# Sensor_Schem.net
KiCad netlist of a schematic drawn in Altium Designer
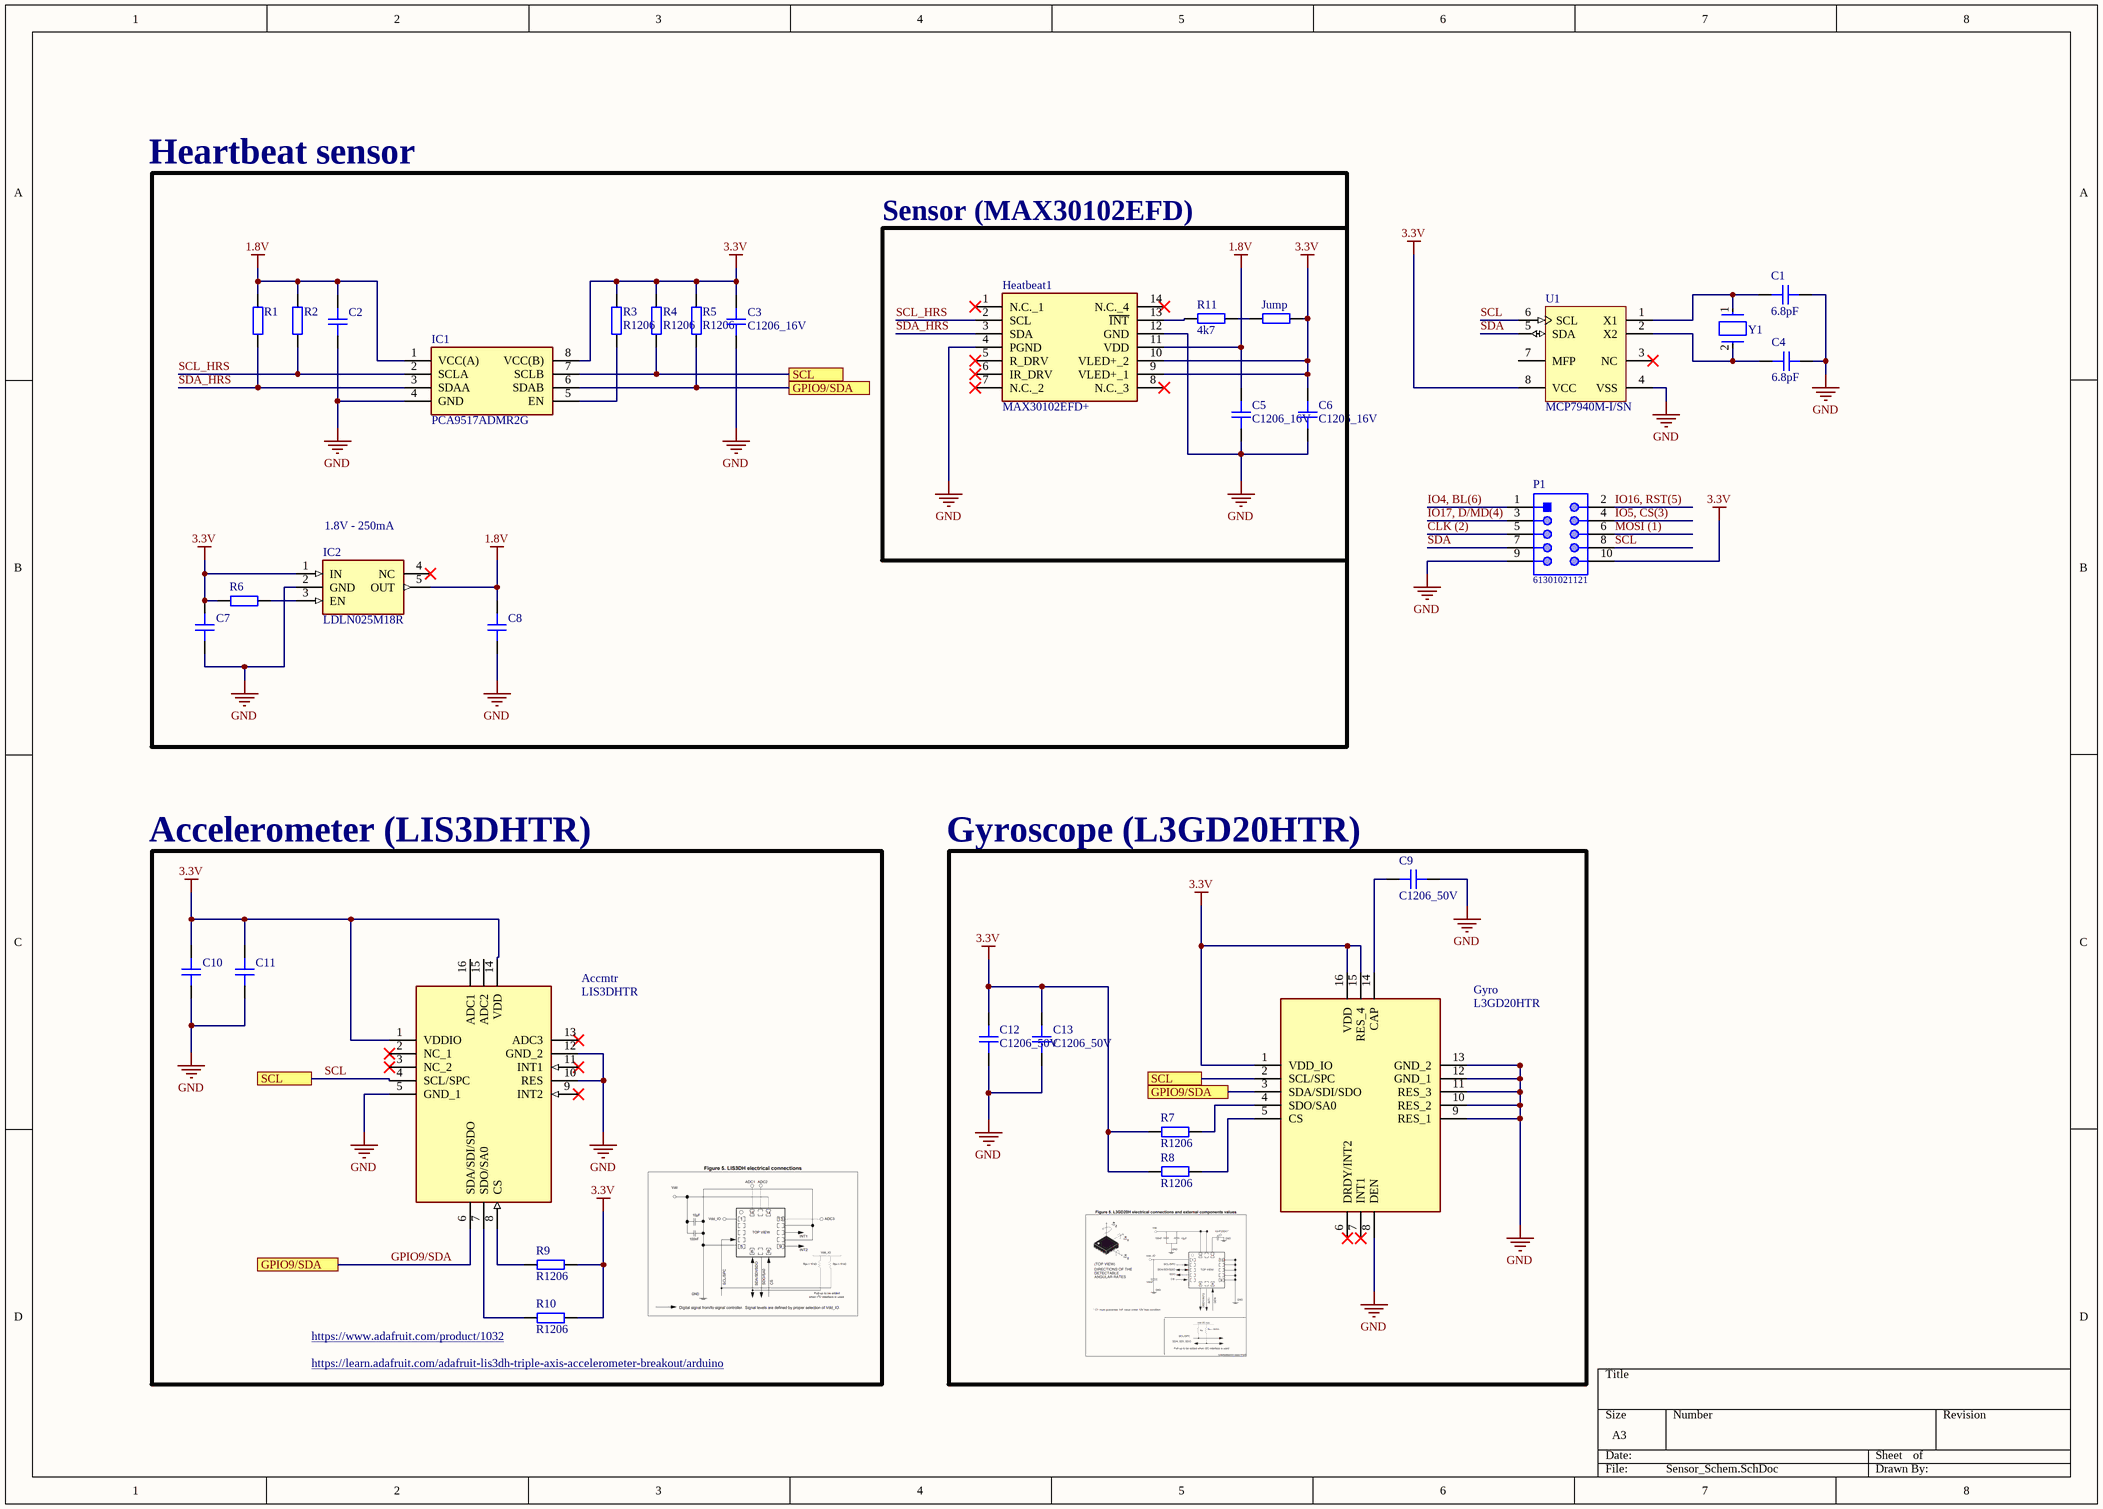
[diagram p0: Sensor_Schem.SchDoc]

(export (version "E")
  (design (tool "Eeschema 10.0.6"))
  (components
    (comp (ref "Accmtr")
      (value "LIS3DHTR")
      (footprint "LIS3DHTR")
      (description "Accelerometer")
      (fields (field (name "MOUSER PART NUMBER") "511-LIS3DHTR"))
      (libsource (lib "Schem_Lib_DaanHeetkamp.") (part "LIS3DHTR"))
    )
    (comp (ref "C1")
      (value "6.8pF")
      (footprint "CAP_1206")
      (description "Capacitor SMD 1206 50V")
      (libsource (lib "Schem_Lib_DaanHeetkamp.") (part "CAP_1206_50V"))
    )
    (comp (ref "C2")
      (value "C1206_16V")
      (footprint "CAP_1206")
      (description "Capacitor SMD 1206 16V")
      (libsource (lib "Schem_Lib_DaanHeetkamp.") (part "CAP_1206_16V"))
    )
    (comp (ref "C3")
      (value "C1206_16V")
      (footprint "CAP_1206")
      (description "Capacitor SMD 1206 16V")
      (libsource (lib "Schem_Lib_DaanHeetkamp.") (part "CAP_1206_16V"))
    )
    (comp (ref "C4")
      (value "6.8pF")
      (footprint "CAP_1206")
      (description "Capacitor SMD 1206 50V")
      (libsource (lib "Schem_Lib_DaanHeetkamp.") (part "CAP_1206_50V"))
    )
    (comp (ref "C5")
      (value "C1206_16V")
      (footprint "CAP_1206")
      (description "Capacitor SMD 1206 16V")
      (libsource (lib "Schem_Lib_DaanHeetkamp.") (part "CAP_1206_16V"))
    )
    (comp (ref "C6")
      (value "C1206_16V")
      (footprint "CAP_1206")
      (description "Capacitor SMD 1206 16V")
      (libsource (lib "Schem_Lib_DaanHeetkamp.") (part "CAP_1206_16V"))
    )
    (comp (ref "C7")
      (value "C1206_16V")
      (footprint "CAP_1206")
      (description "Capacitor SMD 1206 16V")
      (libsource (lib "Schem_Lib_DaanHeetkamp.") (part "CAP_1206_16V"))
    )
    (comp (ref "C8")
      (value "C1206_16V")
      (footprint "CAP_1206")
      (description "Capacitor SMD 1206 16V")
      (libsource (lib "Schem_Lib_DaanHeetkamp.") (part "CAP_1206_16V"))
    )
    (comp (ref "C9")
      (value "C1206_50V")
      (footprint "CAP_1206")
      (description "Capacitor SMD 1206 50V")
      (libsource (lib "Schem_Lib_DaanHeetkamp.") (part "CAP_1206_50V"))
    )
    (comp (ref "C10")
      (value "C1206_50V")
      (footprint "CAP_1206")
      (description "Capacitor SMD 1206 50V")
      (libsource (lib "Schem_Lib_DaanHeetkamp.") (part "CAP_1206_50V"))
    )
    (comp (ref "C11")
      (value "C1206_50V")
      (footprint "CAP_1206")
      (description "Capacitor SMD 1206 50V")
      (libsource (lib "Schem_Lib_DaanHeetkamp.") (part "CAP_1206_50V"))
    )
    (comp (ref "C12")
      (value "C1206_50V")
      (footprint "CAP_1206")
      (description "Capacitor SMD 1206 50V")
      (libsource (lib "Schem_Lib_DaanHeetkamp.") (part "CAP_1206_50V"))
    )
    (comp (ref "C13")
      (value "C1206_50V")
      (footprint "CAP_1206")
      (description "Capacitor SMD 1206 50V")
      (libsource (lib "Schem_Lib_DaanHeetkamp.") (part "CAP_1206_50V"))
    )
    (comp (ref "Gyro")
      (value "L3GD20HTR")
      (footprint "H3LIS100DLTR")
      (description "MEMS motion sensor:\r\n three-axis digital output gyroscope")
      (fields (field (name "MOUSER PART NUMBER") "511-L3GD20HTR"))
      (libsource (lib "Schem_Lib_DaanHeetkamp.") (part "L3GD20HTR"))
    )
    (comp (ref "Heatbeat1")
      (value "MAX30102EFD+")
      (footprint "14-LEAD-OESIP")
      (description "Integrated Circuit")
      (fields (field (name "MOUSER PART NUMBER") "700-MAX30102EFD+"))
      (libsource (lib "Schem_Lib_DaanHeetkamp.") (part "MAX30102EFD+"))
    )
    (comp (ref "IC1")
      (value "PCA9517ADMR2G")
      (footprint "SOP65P490X110-8N")
      (description "Integrated Circuit")
      (fields (field (name "MOUSER PART NUMBER") "863-PCA9517ADMR2G"))
      (libsource (lib "Schem_Lib_DaanHeetkamp.") (part "PCA9517ADMR2G"))
    )
    (comp (ref "IC2")
      (value "LDLN025M18R")
      (footprint "SOT95P280X145-5N")
      (description "Integrated Circuit")
      (fields (field (name "MOUSER PART NUMBER") "511-LDLN025M18R"))
      (libsource (lib "Schem_Lib_DaanHeetkamp.") (part "LDLN025M18R"))
    )
    (comp (ref "Jump")
      (value "R0402")
      (footprint "RES_0402")
      (description "Resistor SMD 0402")
      (libsource (lib "Schem_Lib_DaanHeetkamp.") (part "RES_0402"))
    )
    (comp (ref "P1")
      (value "61301021121")
      (footprint "61301021121")
      (description "THT Vertical Pin Header WR-PHD, Pitch 2.54 mm, Dual Row, 10 pins")
      (fields (field (name "MANUFACTURER") "Wurth Elektronik") (field (name "PUBLISHER") "WurthElektronik"))
      (libsource (lib "Altium Content Vault") (part "WE-CN-2P-M-R10"))
    )
    (comp (ref "R1")
      (value "R1206")
      (footprint "RES_1206")
      (description "Resistor SMD 1206")
      (libsource (lib "Schem_Lib_DaanHeetkamp.") (part "RES_1206"))
    )
    (comp (ref "R2")
      (value "R1206")
      (footprint "RES_1206")
      (description "Resistor SMD 1206")
      (libsource (lib "Schem_Lib_DaanHeetkamp.") (part "RES_1206"))
    )
    (comp (ref "R3")
      (value "R1206")
      (footprint "RES_1206")
      (description "Resistor SMD 1206")
      (libsource (lib "Schem_Lib_DaanHeetkamp.") (part "RES_1206"))
    )
    (comp (ref "R4")
      (value "R1206")
      (footprint "RES_1206")
      (description "Resistor SMD 1206")
      (libsource (lib "Schem_Lib_DaanHeetkamp.") (part "RES_1206"))
    )
    (comp (ref "R5")
      (value "R1206")
      (footprint "RES_1206")
      (description "Resistor SMD 1206")
      (libsource (lib "Schem_Lib_DaanHeetkamp.") (part "RES_1206"))
    )
    (comp (ref "R6")
      (value "R1206")
      (footprint "RES_1206")
      (description "Resistor SMD 1206")
      (libsource (lib "Schem_Lib_DaanHeetkamp.") (part "RES_1206"))
    )
    (comp (ref "R7")
      (value "R1206")
      (footprint "RES_1206")
      (description "Resistor SMD 1206")
      (libsource (lib "Schem_Lib_DaanHeetkamp.") (part "RES_1206"))
    )
    (comp (ref "R8")
      (value "R1206")
      (footprint "RES_1206")
      (description "Resistor SMD 1206")
      (libsource (lib "Schem_Lib_DaanHeetkamp.") (part "RES_1206"))
    )
    (comp (ref "R9")
      (value "R1206")
      (footprint "RES_1206")
      (description "Resistor SMD 1206")
      (libsource (lib "Schem_Lib_DaanHeetkamp.") (part "RES_1206"))
    )
    (comp (ref "R10")
      (value "R1206")
      (footprint "RES_1206")
      (description "Resistor SMD 1206")
      (libsource (lib "Schem_Lib_DaanHeetkamp.") (part "RES_1206"))
    )
    (comp (ref "R11")
      (value "4k7")
      (footprint "RES_1206")
      (description "Resistor SMD 1206")
      (libsource (lib "Schem_Lib_DaanHeetkamp.") (part "RES_1206"))
    )
    (comp (ref "U1")
      (value "MCP7940M-I/SN")
      (footprint "MCHP-SOIC-SN8_L")
      (fields (field (name "MANUFACTURER") "Microchip"))
      (libsource (lib "Altium Content Vault") (part "MCHP-MCP7940M-xx-8"))
    )
    (comp (ref "Y1")
      (value "ABS07-120-32.768KHZ-T")
      (footprint "FP-ABS07-120-MFG")
      (description "CRYSTAL 32.7680KHZ 6PF SMD")
      (fields (field (name "TOLERANCE") "20ppm"))
      (libsource (lib "Altium Content Vault") (part "c23a69dc6c9e2f18f2079038eb95dd1"))
    )
  )
  (nets
    (net (code "1") (name "/CLK (2)") (class "Default")
      (node (ref "P1") (pin "5") (pinfunction "5_5") (pintype "passive"))
    )
    (net (code "2") (name "/GPIO9{slash}SDA") (class "Default")
      (node (ref "Accmtr") (pin "6") (pinfunction "SDA/SDI/SDO_6") (pintype "passive"))
      (node (ref "Gyro") (pin "3") (pinfunction "SDA/SDI/SDO_3") (pintype "passive"))
      (node (ref "IC1") (pin "6") (pinfunction "SDAB_6") (pintype "passive"))
      (node (ref "R5") (pin "2") (pinfunction "2_2") (pintype "passive"))
    )
    (net (code "3") (name "/IO4, BL(6)") (class "Default")
      (node (ref "P1") (pin "1") (pinfunction "1_1") (pintype "passive"))
    )
    (net (code "4") (name "/IO5, CS(3)") (class "Default")
      (node (ref "P1") (pin "4") (pinfunction "4_4") (pintype "passive"))
    )
    (net (code "5") (name "/IO16, RST(5)") (class "Default")
      (node (ref "P1") (pin "2") (pinfunction "2_2") (pintype "passive"))
    )
    (net (code "6") (name "/IO17, D{slash}MD(4)") (class "Default")
      (node (ref "P1") (pin "3") (pinfunction "3_3") (pintype "passive"))
    )
    (net (code "7") (name "/MOSI (1)") (class "Default")
      (node (ref "P1") (pin "6") (pinfunction "6_6") (pintype "passive"))
    )
    (net (code "8") (name "/SCL") (class "Default")
      (node (ref "Accmtr") (pin "4") (pinfunction "SCL/SPC_4") (pintype "passive"))
      (node (ref "Gyro") (pin "2") (pinfunction "SCL/SPC_2") (pintype "passive"))
      (node (ref "IC1") (pin "7") (pinfunction "SCLB_7") (pintype "passive"))
      (node (ref "P1") (pin "8") (pinfunction "8_8") (pintype "passive"))
      (node (ref "R4") (pin "2") (pinfunction "2_2") (pintype "passive"))
      (node (ref "U1") (pin "6") (pinfunction "SCL_6") (pintype "input"))
    )
    (net (code "9") (name "/SCL_HRS") (class "Default")
      (node (ref "Heatbeat1") (pin "2") (pinfunction "SCL_2") (pintype "passive"))
      (node (ref "IC1") (pin "2") (pinfunction "SCLA_2") (pintype "passive"))
      (node (ref "R2") (pin "2") (pinfunction "2_2") (pintype "passive"))
    )
    (net (code "10") (name "/SDA") (class "Default")
      (node (ref "P1") (pin "7") (pinfunction "7_7") (pintype "passive"))
      (node (ref "U1") (pin "5") (pinfunction "SDA_5") (pintype "bidirectional"))
    )
    (net (code "11") (name "/SDA_HRS") (class "Default")
      (node (ref "Heatbeat1") (pin "3") (pinfunction "SDA_3") (pintype "passive"))
      (node (ref "IC1") (pin "3") (pinfunction "SDAA_3") (pintype "passive"))
      (node (ref "R1") (pin "2") (pinfunction "2_2") (pintype "passive"))
    )
    (net (code "12") (name "1.8V") (class "Default")
      (node (ref "C2") (pin "2") (pinfunction "2_2") (pintype "passive"))
      (node (ref "C5") (pin "2") (pinfunction "2_2") (pintype "passive"))
      (node (ref "C8") (pin "2") (pinfunction "2_2") (pintype "passive"))
      (node (ref "Heatbeat1") (pin "11") (pinfunction "VDD_11") (pintype "passive"))
      (node (ref "IC1") (pin "1") (pinfunction "VCC(A)_1") (pintype "passive"))
      (node (ref "IC2") (pin "5") (pinfunction "OUT_5") (pintype "output"))
      (node (ref "R1") (pin "1") (pinfunction "1_1") (pintype "passive"))
      (node (ref "R2") (pin "1") (pinfunction "1_1") (pintype "passive"))
    )
    (net (code "13") (name "3.3V") (class "Default")
      (node (ref "Accmtr") (pin "1") (pinfunction "VDDIO_1") (pintype "power_in"))
      (node (ref "Accmtr") (pin "14") (pinfunction "VDD_14") (pintype "power_in"))
      (node (ref "C10") (pin "2") (pinfunction "2_2") (pintype "passive"))
      (node (ref "C11") (pin "2") (pinfunction "2_2") (pintype "passive"))
      (node (ref "C12") (pin "2") (pinfunction "2_2") (pintype "passive"))
      (node (ref "C13") (pin "2") (pinfunction "2_2") (pintype "passive"))
      (node (ref "C3") (pin "2") (pinfunction "2_2") (pintype "passive"))
      (node (ref "C6") (pin "2") (pinfunction "2_2") (pintype "passive"))
      (node (ref "C7") (pin "2") (pinfunction "2_2") (pintype "passive"))
      (node (ref "Gyro") (pin "1") (pinfunction "VDD_IO_1") (pintype "passive"))
      (node (ref "Gyro") (pin "15") (pinfunction "RES_4_15") (pintype "passive"))
      (node (ref "Gyro") (pin "16") (pinfunction "VDD_16") (pintype "passive"))
      (node (ref "Heatbeat1") (pin "10") (pinfunction "VLED+_2_10") (pintype "passive"))
      (node (ref "Heatbeat1") (pin "9") (pinfunction "VLED+_1_9") (pintype "passive"))
      (node (ref "IC1") (pin "8") (pinfunction "VCC(B)_8") (pintype "passive"))
      (node (ref "IC2") (pin "1") (pinfunction "IN_1") (pintype "input"))
      (node (ref "Jump") (pin "2") (pinfunction "2_2") (pintype "passive"))
      (node (ref "P1") (pin "10") (pinfunction "10_10") (pintype "passive"))
      (node (ref "R10") (pin "1") (pinfunction "1_1") (pintype "passive"))
      (node (ref "R3") (pin "1") (pinfunction "1_1") (pintype "passive"))
      (node (ref "R4") (pin "1") (pinfunction "1_1") (pintype "passive"))
      (node (ref "R5") (pin "1") (pinfunction "1_1") (pintype "passive"))
      (node (ref "R6") (pin "1") (pinfunction "1_1") (pintype "passive"))
      (node (ref "R7") (pin "2") (pinfunction "2_2") (pintype "passive"))
      (node (ref "R8") (pin "2") (pinfunction "2_2") (pintype "passive"))
      (node (ref "R9") (pin "1") (pinfunction "1_1") (pintype "passive"))
      (node (ref "U1") (pin "8") (pinfunction "VCC_8") (pintype "power_in"))
    )
    (net (code "14") (name "GND") (class "Default")
      (node (ref "Accmtr") (pin "10") (pinfunction "RES_10") (pintype "passive"))
      (node (ref "Accmtr") (pin "12") (pinfunction "GND_2_12") (pintype "power_in"))
      (node (ref "Accmtr") (pin "5") (pinfunction "GND_1_5") (pintype "power_in"))
      (node (ref "C1") (pin "2") (pinfunction "2_2") (pintype "passive"))
      (node (ref "C10") (pin "1") (pinfunction "1_1") (pintype "passive"))
      (node (ref "C11") (pin "1") (pinfunction "1_1") (pintype "passive"))
      (node (ref "C12") (pin "1") (pinfunction "1_1") (pintype "passive"))
      (node (ref "C13") (pin "1") (pinfunction "1_1") (pintype "passive"))
      (node (ref "C2") (pin "1") (pinfunction "1_1") (pintype "passive"))
      (node (ref "C3") (pin "1") (pinfunction "1_1") (pintype "passive"))
      (node (ref "C4") (pin "2") (pinfunction "2_2") (pintype "passive"))
      (node (ref "C5") (pin "1") (pinfunction "1_1") (pintype "passive"))
      (node (ref "C6") (pin "1") (pinfunction "1_1") (pintype "passive"))
      (node (ref "C7") (pin "1") (pinfunction "1_1") (pintype "passive"))
      (node (ref "C8") (pin "1") (pinfunction "1_1") (pintype "passive"))
      (node (ref "C9") (pin "2") (pinfunction "2_2") (pintype "passive"))
      (node (ref "Gyro") (pin "10") (pinfunction "RES_2_10") (pintype "passive"))
      (node (ref "Gyro") (pin "11") (pinfunction "RES_3_11") (pintype "passive"))
      (node (ref "Gyro") (pin "12") (pinfunction "GND_1_12") (pintype "passive"))
      (node (ref "Gyro") (pin "13") (pinfunction "GND_2_13") (pintype "passive"))
      (node (ref "Gyro") (pin "8") (pinfunction "DEN_8") (pintype "passive"))
      (node (ref "Gyro") (pin "9") (pinfunction "RES_1_9") (pintype "passive"))
      (node (ref "Heatbeat1") (pin "12") (pinfunction "GND_12") (pintype "passive"))
      (node (ref "Heatbeat1") (pin "4") (pinfunction "PGND_4") (pintype "passive"))
      (node (ref "IC1") (pin "4") (pinfunction "GND_4") (pintype "passive"))
      (node (ref "IC2") (pin "2") (pinfunction "GND_2") (pintype "power_in"))
      (node (ref "P1") (pin "9") (pinfunction "9_9") (pintype "passive"))
      (node (ref "U1") (pin "4") (pinfunction "VSS_4") (pintype "power_in"))
    )
    (net (code "15") (name "Net-(Accmtr-CS)") (class "Default")
      (node (ref "Accmtr") (pin "8") (pinfunction "CS_8") (pintype "input"))
      (node (ref "R9") (pin "2") (pinfunction "2_2") (pintype "passive"))
    )
    (net (code "16") (name "Net-(Accmtr-SDO{slash}SA0)") (class "Default")
      (node (ref "Accmtr") (pin "7") (pinfunction "SDO/SA0_7") (pintype "passive"))
      (node (ref "R10") (pin "2") (pinfunction "2_2") (pintype "passive"))
    )
    (net (code "17") (name "Net-(Gyro-CAP)") (class "Default")
      (node (ref "C9") (pin "1") (pinfunction "1_1") (pintype "passive"))
      (node (ref "Gyro") (pin "14") (pinfunction "CAP_14") (pintype "passive"))
    )
    (net (code "18") (name "Net-(Gyro-CS)") (class "Default")
      (node (ref "Gyro") (pin "5") (pinfunction "CS_5") (pintype "passive"))
      (node (ref "R8") (pin "1") (pinfunction "1_1") (pintype "passive"))
    )
    (net (code "19") (name "Net-(Gyro-SDO{slash}SA0)") (class "Default")
      (node (ref "Gyro") (pin "4") (pinfunction "SDO/SA0_4") (pintype "passive"))
      (node (ref "R7") (pin "1") (pinfunction "1_1") (pintype "passive"))
    )
    (net (code "20") (name "Net-(Heatbeat1-~{INT})") (class "Default")
      (node (ref "Heatbeat1") (pin "13") (pinfunction "~{INT}_13") (pintype "passive"))
      (node (ref "R11") (pin "2") (pinfunction "2_2") (pintype "passive"))
    )
    (net (code "21") (name "Net-(IC1-EN)") (class "Default")
      (node (ref "IC1") (pin "5") (pinfunction "EN_5") (pintype "passive"))
      (node (ref "R3") (pin "2") (pinfunction "2_2") (pintype "passive"))
    )
    (net (code "22") (name "Net-(IC2-EN)") (class "Default")
      (node (ref "IC2") (pin "3") (pinfunction "EN_3") (pintype "input"))
      (node (ref "R6") (pin "2") (pinfunction "2_2") (pintype "passive"))
    )
    (net (code "23") (name "Net-(Jump-Pad1)") (class "Default")
      (node (ref "Jump") (pin "1") (pinfunction "1_1") (pintype "passive"))
      (node (ref "R11") (pin "1") (pinfunction "1_1") (pintype "passive"))
    )
    (net (code "24") (name "Net-(U1-X1)") (class "Default")
      (node (ref "C1") (pin "1") (pinfunction "1_1") (pintype "passive"))
      (node (ref "U1") (pin "1") (pinfunction "X1_1") (pintype "passive"))
      (node (ref "Y1") (pin "1") (pinfunction "1_1") (pintype "passive"))
    )
    (net (code "25") (name "Net-(U1-X2)") (class "Default")
      (node (ref "C4") (pin "1") (pinfunction "1_1") (pintype "passive"))
      (node (ref "U1") (pin "2") (pinfunction "X2_2") (pintype "passive"))
      (node (ref "Y1") (pin "2") (pinfunction "2_2") (pintype "passive"))
    )
    (net (code "26") (name "unconnected-(Accmtr-ADC1-Pad16)") (class "Default")
      (node (ref "Accmtr") (pin "16") (pinfunction "ADC1_16") (pintype "passive"))
    )
    (net (code "27") (name "unconnected-(Accmtr-ADC2-Pad15)") (class "Default")
      (node (ref "Accmtr") (pin "15") (pinfunction "ADC2_15") (pintype "passive"))
    )
    (net (code "28") (name "unconnected-(Accmtr-ADC3-Pad13)") (class "Default")
      (node (ref "Accmtr") (pin "13") (pinfunction "ADC3_13") (pintype "passive+no_connect"))
    )
    (net (code "29") (name "unconnected-(Accmtr-INT1-Pad11)") (class "Default")
      (node (ref "Accmtr") (pin "11") (pinfunction "INT1_11") (pintype "input+no_connect"))
    )
    (net (code "30") (name "unconnected-(Accmtr-INT2-Pad9)") (class "Default")
      (node (ref "Accmtr") (pin "9") (pinfunction "INT2_9") (pintype "input+no_connect"))
    )
    (net (code "31") (name "unconnected-(Accmtr-NC_1-Pad2)") (class "Default")
      (node (ref "Accmtr") (pin "2") (pinfunction "NC_1_2") (pintype "passive+no_connect"))
    )
    (net (code "32") (name "unconnected-(Accmtr-NC_2-Pad3)") (class "Default")
      (node (ref "Accmtr") (pin "3") (pinfunction "NC_2_3") (pintype "passive+no_connect"))
    )
    (net (code "33") (name "unconnected-(Gyro-DRDY{slash}INT2-Pad6)") (class "Default")
      (node (ref "Gyro") (pin "6") (pinfunction "DRDY/INT2_6") (pintype "passive+no_connect"))
    )
    (net (code "34") (name "unconnected-(Gyro-INT1-Pad7)") (class "Default")
      (node (ref "Gyro") (pin "7") (pinfunction "INT1_7") (pintype "passive+no_connect"))
    )
    (net (code "35") (name "unconnected-(Heatbeat1-IR_DRV-Pad6)") (class "Default")
      (node (ref "Heatbeat1") (pin "6") (pinfunction "IR_DRV_6") (pintype "passive+no_connect"))
    )
    (net (code "36") (name "unconnected-(Heatbeat1-N.C._1-Pad1)") (class "Default")
      (node (ref "Heatbeat1") (pin "1") (pinfunction "N.C._1_1") (pintype "passive+no_connect"))
    )
    (net (code "37") (name "unconnected-(Heatbeat1-N.C._2-Pad7)") (class "Default")
      (node (ref "Heatbeat1") (pin "7") (pinfunction "N.C._2_7") (pintype "passive+no_connect"))
    )
    (net (code "38") (name "unconnected-(Heatbeat1-N.C._3-Pad8)") (class "Default")
      (node (ref "Heatbeat1") (pin "8") (pinfunction "N.C._3_8") (pintype "passive+no_connect"))
    )
    (net (code "39") (name "unconnected-(Heatbeat1-N.C._4-Pad14)") (class "Default")
      (node (ref "Heatbeat1") (pin "14") (pinfunction "N.C._4_14") (pintype "passive+no_connect"))
    )
    (net (code "40") (name "unconnected-(Heatbeat1-R_DRV-Pad5)") (class "Default")
      (node (ref "Heatbeat1") (pin "5") (pinfunction "R_DRV_5") (pintype "passive+no_connect"))
    )
    (net (code "41") (name "unconnected-(IC2-NC-Pad4)") (class "Default")
      (node (ref "IC2") (pin "4") (pinfunction "NC_4") (pintype "passive+no_connect"))
    )
    (net (code "42") (name "unconnected-(U1-MFP-Pad7)") (class "Default")
      (node (ref "U1") (pin "7") (pinfunction "MFP_7") (pintype "open_collector"))
    )
    (net (code "43") (name "unconnected-(U1-NC-Pad3)") (class "Default")
      (node (ref "U1") (pin "3") (pinfunction "NC_3") (pintype "passive+no_connect"))
    )
  )
)
